# TowerLight.net
KiCad netlist of a schematic drawn in EAGLE
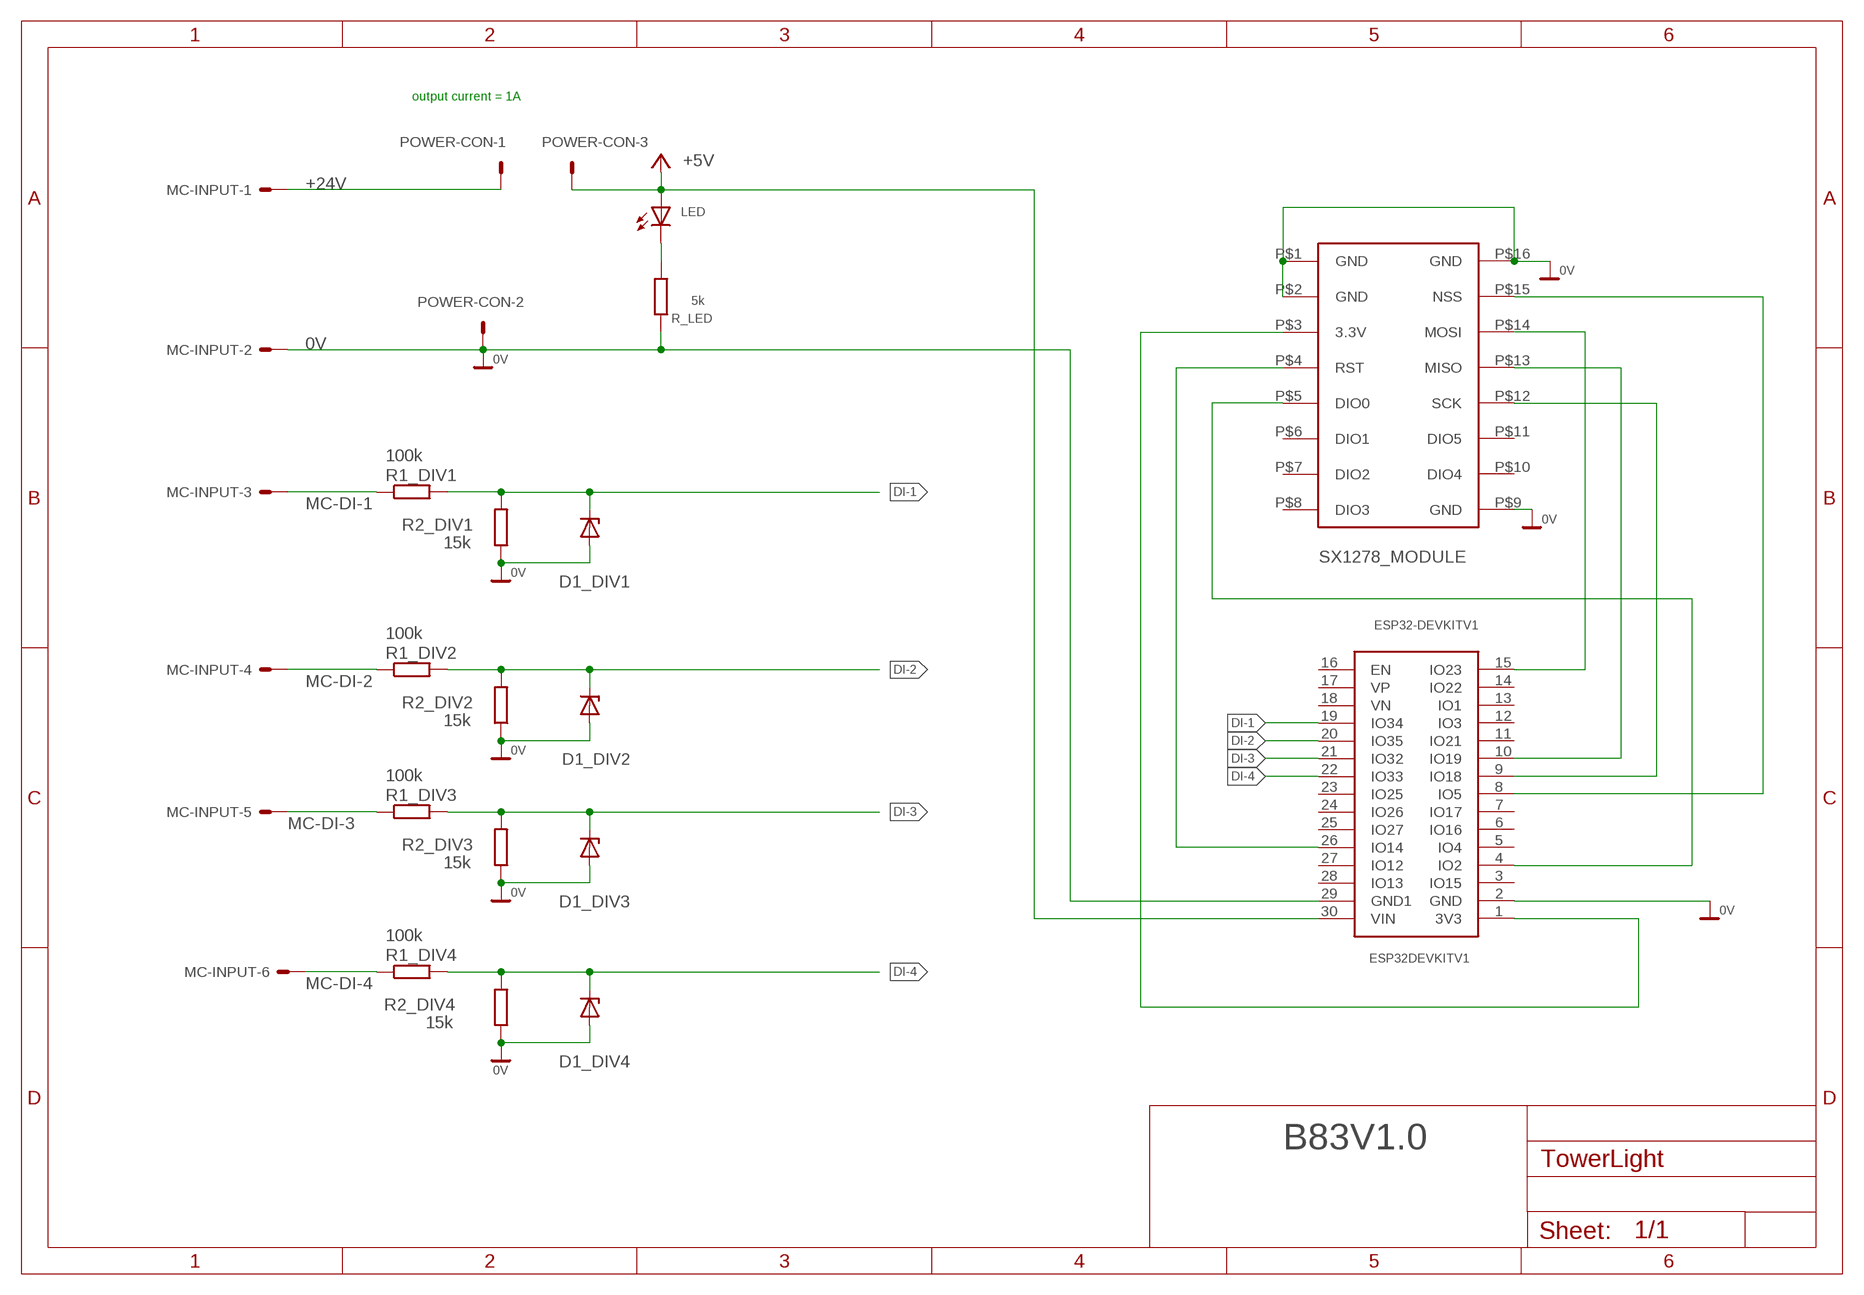
[diagram p0: schematic, sheet 1]

(export (version "E")
  (design (tool "Eeschema 10.0.6"))
  (components
    (comp (ref "D1_DIV1")
      (value "ZENER-DIODEDO34-7")
      (footprint "eagle-import:DO34Z7")
      (libsource (lib "eagle-import") (part "ZENER-DIODEDO34-7"))
    )
    (comp (ref "D1_DIV2")
      (value "ZENER-DIODEDO34-7")
      (footprint "eagle-import:DO34Z7")
      (libsource (lib "eagle-import") (part "ZENER-DIODEDO34-7"))
    )
    (comp (ref "D1_DIV3")
      (value "ZENER-DIODEDO34-7")
      (footprint "eagle-import:DO34Z7")
      (libsource (lib "eagle-import") (part "ZENER-DIODEDO34-7"))
    )
    (comp (ref "D1_DIV4")
      (value "ZENER-DIODEDO34-7")
      (footprint "eagle-import:DO34Z7")
      (libsource (lib "eagle-import") (part "ZENER-DIODEDO34-7"))
    )
    (comp (ref "ESP32DEVKITV1")
      (value "ESP32DEVKITV1")
      (footprint "eagle-import:ESP32-DEVKITV1")
      (libsource (lib "eagle-import") (part "ESP32DEVKITV1"))
    )
    (comp (ref "LED")
      (value "LED_SUB")
      (footprint "eagle-import:LED_SUBMINI")
      (libsource (lib "eagle-import") (part "LED_SUB"))
    )
    (comp (ref "MC-INPUT")
      (value "22-05-7068-06")
      (footprint "eagle-import:7395-06")
      (libsource (lib "eagle-import") (part "22-?-0605-7068"))
    )
    (comp (ref "POWER-CON")
      (value "22-05-7038-03")
      (footprint "eagle-import:7395-03")
      (libsource (lib "eagle-import") (part "22-?-0305-7038"))
    )
    (comp (ref "R1_DIV1")
      (value "100k")
      (footprint "eagle-import:R1206")
      (libsource (lib "eagle-import") (part "R-EU_R1206"))
    )
    (comp (ref "R1_DIV2")
      (value "100k")
      (footprint "eagle-import:R1206")
      (libsource (lib "eagle-import") (part "R-EU_R1206"))
    )
    (comp (ref "R1_DIV3")
      (value "100k")
      (footprint "eagle-import:R1206")
      (libsource (lib "eagle-import") (part "R-EU_R1206"))
    )
    (comp (ref "R1_DIV4")
      (value "100k")
      (footprint "eagle-import:R1206")
      (libsource (lib "eagle-import") (part "R-EU_R1206"))
    )
    (comp (ref "R2_DIV1")
      (value "15k")
      (footprint "eagle-import:R1206")
      (libsource (lib "eagle-import") (part "R-EU_R1206"))
    )
    (comp (ref "R2_DIV2")
      (value "15k")
      (footprint "eagle-import:R1206")
      (libsource (lib "eagle-import") (part "R-EU_R1206"))
    )
    (comp (ref "R2_DIV3")
      (value "15k")
      (footprint "eagle-import:R1206")
      (libsource (lib "eagle-import") (part "R-EU_R1206"))
    )
    (comp (ref "R2_DIV4")
      (value "15k")
      (footprint "eagle-import:R1206")
      (libsource (lib "eagle-import") (part "R-EU_R1206"))
    )
    (comp (ref "R_LED")
      (value "5k")
      (footprint "eagle-import:R1206")
      (libsource (lib "eagle-import") (part "R-EU_R1206"))
    )
    (comp (ref "U$2")
      (value "LORA-02_SX1278_MODULE")
      (footprint "eagle-import:LORA-02_SX1278_MODULE")
      (libsource (lib "eagle-import") (part "LORA-02_SX1278_MODULE"))
    )
  )
  (nets
    (net (code "1") (name "+5V") (class "Default")
      (node (ref "ESP32DEVKITV1") (pin "30") (pinfunction "VIN_30") (pintype "bidirectional"))
      (node (ref "LED") (pin "P$1") (pinfunction "A_P$1") (pintype "passive"))
      (node (ref "POWER-CON") (pin "3") (pinfunction "S_3") (pintype "passive"))
    )
    (net (code "2") (name "/+24V") (class "Default")
      (node (ref "MC-INPUT") (pin "1") (pinfunction "S_1") (pintype "passive"))
      (node (ref "POWER-CON") (pin "1") (pinfunction "S_1") (pintype "passive"))
    )
    (net (code "3") (name "/MC-DI-1") (class "Default")
      (node (ref "MC-INPUT") (pin "3") (pinfunction "S_3") (pintype "passive"))
      (node (ref "R1_DIV1") (pin "1") (pinfunction "1_1") (pintype "passive"))
    )
    (net (code "4") (name "/MC-DI-2") (class "Default")
      (node (ref "MC-INPUT") (pin "4") (pinfunction "S_4") (pintype "passive"))
      (node (ref "R1_DIV2") (pin "1") (pinfunction "1_1") (pintype "passive"))
    )
    (net (code "5") (name "/MC-DI-3") (class "Default")
      (node (ref "MC-INPUT") (pin "5") (pinfunction "S_5") (pintype "passive"))
      (node (ref "R1_DIV3") (pin "1") (pinfunction "1_1") (pintype "passive"))
    )
    (net (code "6") (name "/MC-DI-4") (class "Default")
      (node (ref "MC-INPUT") (pin "6") (pinfunction "S_6") (pintype "passive"))
      (node (ref "R1_DIV4") (pin "1") (pinfunction "1_1") (pintype "passive"))
    )
    (net (code "7") (name "0V") (class "Default")
      (node (ref "D1_DIV1") (pin "A") (pinfunction "A_A") (pintype "passive"))
      (node (ref "D1_DIV2") (pin "A") (pinfunction "A_A") (pintype "passive"))
      (node (ref "D1_DIV3") (pin "A") (pinfunction "A_A") (pintype "passive"))
      (node (ref "D1_DIV4") (pin "A") (pinfunction "A_A") (pintype "passive"))
      (node (ref "ESP32DEVKITV1") (pin "2") (pinfunction "GND_2") (pintype "bidirectional"))
      (node (ref "ESP32DEVKITV1") (pin "29") (pinfunction "GND1_29") (pintype "bidirectional"))
      (node (ref "MC-INPUT") (pin "2") (pinfunction "S_2") (pintype "passive"))
      (node (ref "POWER-CON") (pin "2") (pinfunction "S_2") (pintype "passive"))
      (node (ref "R2_DIV1") (pin "1") (pinfunction "1_1") (pintype "passive"))
      (node (ref "R2_DIV2") (pin "1") (pinfunction "1_1") (pintype "passive"))
      (node (ref "R2_DIV3") (pin "1") (pinfunction "1_1") (pintype "passive"))
      (node (ref "R2_DIV4") (pin "1") (pinfunction "1_1") (pintype "passive"))
      (node (ref "R_LED") (pin "2") (pinfunction "2_2") (pintype "passive"))
      (node (ref "U$2") (pin "P$1") (pinfunction "GND_P$1") (pintype "bidirectional"))
      (node (ref "U$2") (pin "P$16") (pinfunction "GND_P$16") (pintype "bidirectional"))
      (node (ref "U$2") (pin "P$2") (pinfunction "GND_P$2") (pintype "bidirectional"))
      (node (ref "U$2") (pin "P$9") (pinfunction "GND_P$9") (pintype "bidirectional"))
    )
    (net (code "8") (name "DI-1") (class "Default")
      (node (ref "D1_DIV1") (pin "C") (pinfunction "C_C") (pintype "passive"))
      (node (ref "ESP32DEVKITV1") (pin "19") (pinfunction "IO34_19") (pintype "bidirectional"))
      (node (ref "R1_DIV1") (pin "2") (pinfunction "2_2") (pintype "passive"))
      (node (ref "R2_DIV1") (pin "2") (pinfunction "2_2") (pintype "passive"))
    )
    (net (code "9") (name "DI-2") (class "Default")
      (node (ref "D1_DIV2") (pin "C") (pinfunction "C_C") (pintype "passive"))
      (node (ref "ESP32DEVKITV1") (pin "20") (pinfunction "IO35_20") (pintype "bidirectional"))
      (node (ref "R1_DIV2") (pin "2") (pinfunction "2_2") (pintype "passive"))
      (node (ref "R2_DIV2") (pin "2") (pinfunction "2_2") (pintype "passive"))
    )
    (net (code "10") (name "DI-3") (class "Default")
      (node (ref "D1_DIV3") (pin "C") (pinfunction "C_C") (pintype "passive"))
      (node (ref "ESP32DEVKITV1") (pin "21") (pinfunction "IO32_21") (pintype "bidirectional"))
      (node (ref "R1_DIV3") (pin "2") (pinfunction "2_2") (pintype "passive"))
      (node (ref "R2_DIV3") (pin "2") (pinfunction "2_2") (pintype "passive"))
    )
    (net (code "11") (name "DI-4") (class "Default")
      (node (ref "D1_DIV4") (pin "C") (pinfunction "C_C") (pintype "passive"))
      (node (ref "ESP32DEVKITV1") (pin "22") (pinfunction "IO33_22") (pintype "bidirectional"))
      (node (ref "R1_DIV4") (pin "2") (pinfunction "2_2") (pintype "passive"))
      (node (ref "R2_DIV4") (pin "2") (pinfunction "2_2") (pintype "passive"))
    )
    (net (code "12") (name "Net-(ESP32DEVKITV1-3V3)") (class "Default")
      (node (ref "ESP32DEVKITV1") (pin "1") (pinfunction "3V3_1") (pintype "bidirectional"))
      (node (ref "U$2") (pin "P$3") (pinfunction "3.3V_P$3") (pintype "bidirectional"))
    )
    (net (code "13") (name "Net-(ESP32DEVKITV1-IO2)") (class "Default")
      (node (ref "ESP32DEVKITV1") (pin "4") (pinfunction "IO2_4") (pintype "bidirectional"))
      (node (ref "U$2") (pin "P$5") (pinfunction "DIO0_P$5") (pintype "bidirectional"))
    )
    (net (code "14") (name "Net-(ESP32DEVKITV1-IO5)") (class "Default")
      (node (ref "ESP32DEVKITV1") (pin "8") (pinfunction "IO5_8") (pintype "bidirectional"))
      (node (ref "U$2") (pin "P$15") (pinfunction "NSS_P$15") (pintype "bidirectional"))
    )
    (net (code "15") (name "Net-(ESP32DEVKITV1-IO14)") (class "Default")
      (node (ref "ESP32DEVKITV1") (pin "26") (pinfunction "IO14_26") (pintype "bidirectional"))
      (node (ref "U$2") (pin "P$4") (pinfunction "RST_P$4") (pintype "bidirectional"))
    )
    (net (code "16") (name "Net-(ESP32DEVKITV1-IO18)") (class "Default")
      (node (ref "ESP32DEVKITV1") (pin "9") (pinfunction "IO18_9") (pintype "bidirectional"))
      (node (ref "U$2") (pin "P$12") (pinfunction "SCK_P$12") (pintype "bidirectional"))
    )
    (net (code "17") (name "Net-(ESP32DEVKITV1-IO19)") (class "Default")
      (node (ref "ESP32DEVKITV1") (pin "10") (pinfunction "IO19_10") (pintype "bidirectional"))
      (node (ref "U$2") (pin "P$13") (pinfunction "MISO_P$13") (pintype "bidirectional"))
    )
    (net (code "18") (name "Net-(ESP32DEVKITV1-IO23)") (class "Default")
      (node (ref "ESP32DEVKITV1") (pin "15") (pinfunction "IO23_15") (pintype "bidirectional"))
      (node (ref "U$2") (pin "P$14") (pinfunction "MOSI_P$14") (pintype "bidirectional"))
    )
    (net (code "19") (name "Net-(LED-C)") (class "Default")
      (node (ref "LED") (pin "P$2") (pinfunction "C_P$2") (pintype "passive"))
      (node (ref "R_LED") (pin "1") (pinfunction "1_1") (pintype "passive"))
    )
    (net (code "20") (name "unconnected-(ESP32DEVKITV1-EN-Pad16)") (class "Default")
      (node (ref "ESP32DEVKITV1") (pin "16") (pinfunction "EN_16") (pintype "bidirectional"))
    )
    (net (code "21") (name "unconnected-(ESP32DEVKITV1-IO1-Pad13)") (class "Default")
      (node (ref "ESP32DEVKITV1") (pin "13") (pinfunction "IO1_13") (pintype "bidirectional"))
    )
    (net (code "22") (name "unconnected-(ESP32DEVKITV1-IO3-Pad12)") (class "Default")
      (node (ref "ESP32DEVKITV1") (pin "12") (pinfunction "IO3_12") (pintype "bidirectional"))
    )
    (net (code "23") (name "unconnected-(ESP32DEVKITV1-IO4-Pad5)") (class "Default")
      (node (ref "ESP32DEVKITV1") (pin "5") (pinfunction "IO4_5") (pintype "bidirectional"))
    )
    (net (code "24") (name "unconnected-(ESP32DEVKITV1-IO12-Pad27)") (class "Default")
      (node (ref "ESP32DEVKITV1") (pin "27") (pinfunction "IO12_27") (pintype "bidirectional"))
    )
    (net (code "25") (name "unconnected-(ESP32DEVKITV1-IO13-Pad28)") (class "Default")
      (node (ref "ESP32DEVKITV1") (pin "28") (pinfunction "IO13_28") (pintype "bidirectional"))
    )
    (net (code "26") (name "unconnected-(ESP32DEVKITV1-IO15-Pad3)") (class "Default")
      (node (ref "ESP32DEVKITV1") (pin "3") (pinfunction "IO15_3") (pintype "bidirectional"))
    )
    (net (code "27") (name "unconnected-(ESP32DEVKITV1-IO16-Pad6)") (class "Default")
      (node (ref "ESP32DEVKITV1") (pin "6") (pinfunction "IO16_6") (pintype "bidirectional"))
    )
    (net (code "28") (name "unconnected-(ESP32DEVKITV1-IO17-Pad7)") (class "Default")
      (node (ref "ESP32DEVKITV1") (pin "7") (pinfunction "IO17_7") (pintype "bidirectional"))
    )
    (net (code "29") (name "unconnected-(ESP32DEVKITV1-IO21-Pad11)") (class "Default")
      (node (ref "ESP32DEVKITV1") (pin "11") (pinfunction "IO21_11") (pintype "bidirectional"))
    )
    (net (code "30") (name "unconnected-(ESP32DEVKITV1-IO22-Pad14)") (class "Default")
      (node (ref "ESP32DEVKITV1") (pin "14") (pinfunction "IO22_14") (pintype "bidirectional"))
    )
    (net (code "31") (name "unconnected-(ESP32DEVKITV1-IO25-Pad23)") (class "Default")
      (node (ref "ESP32DEVKITV1") (pin "23") (pinfunction "IO25_23") (pintype "bidirectional"))
    )
    (net (code "32") (name "unconnected-(ESP32DEVKITV1-IO26-Pad24)") (class "Default")
      (node (ref "ESP32DEVKITV1") (pin "24") (pinfunction "IO26_24") (pintype "bidirectional"))
    )
    (net (code "33") (name "unconnected-(ESP32DEVKITV1-IO27-Pad25)") (class "Default")
      (node (ref "ESP32DEVKITV1") (pin "25") (pinfunction "IO27_25") (pintype "bidirectional"))
    )
    (net (code "34") (name "unconnected-(ESP32DEVKITV1-VN-Pad18)") (class "Default")
      (node (ref "ESP32DEVKITV1") (pin "18") (pinfunction "VN_18") (pintype "bidirectional"))
    )
    (net (code "35") (name "unconnected-(ESP32DEVKITV1-VP-Pad17)") (class "Default")
      (node (ref "ESP32DEVKITV1") (pin "17") (pinfunction "VP_17") (pintype "bidirectional"))
    )
    (net (code "36") (name "unconnected-(U$2-DIO1-PadP$6)") (class "Default")
      (node (ref "U$2") (pin "P$6") (pinfunction "DIO1_P$6") (pintype "bidirectional"))
    )
    (net (code "37") (name "unconnected-(U$2-DIO2-PadP$7)") (class "Default")
      (node (ref "U$2") (pin "P$7") (pinfunction "DIO2_P$7") (pintype "bidirectional"))
    )
    (net (code "38") (name "unconnected-(U$2-DIO3-PadP$8)") (class "Default")
      (node (ref "U$2") (pin "P$8") (pinfunction "DIO3_P$8") (pintype "bidirectional"))
    )
    (net (code "39") (name "unconnected-(U$2-DIO4-PadP$10)") (class "Default")
      (node (ref "U$2") (pin "P$10") (pinfunction "DIO4_P$10") (pintype "bidirectional"))
    )
    (net (code "40") (name "unconnected-(U$2-DIO5-PadP$11)") (class "Default")
      (node (ref "U$2") (pin "P$11") (pinfunction "DIO5_P$11") (pintype "bidirectional"))
    )
  )
)
